# Osmofl2k_adapter_bandpass.net
KiCad netlist of a schematic drawn in EAGLE
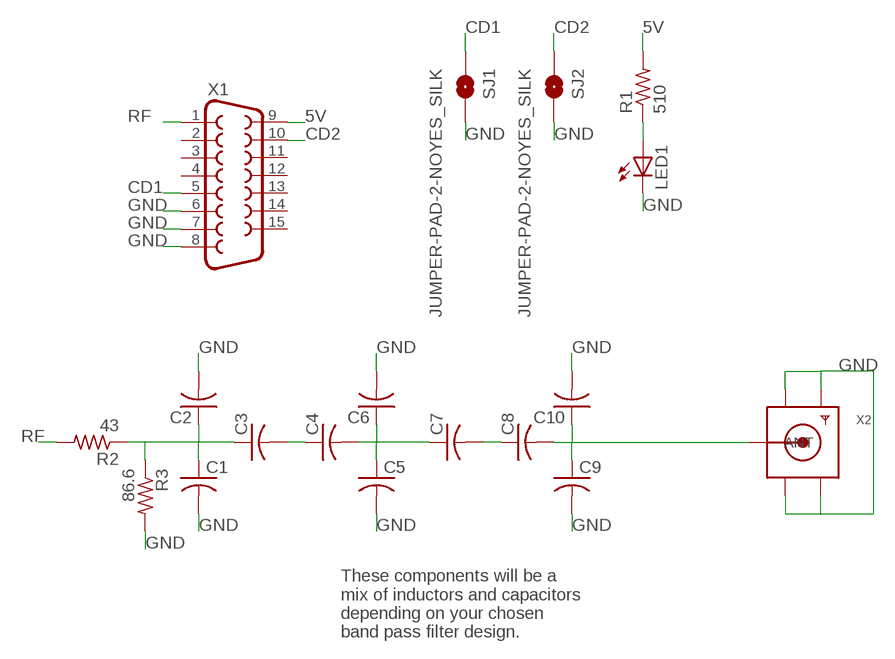
[diagram p0: schematic, sheet 1]

(export (version "E")
  (design (tool "Eeschema 10.0.6"))
  (components
    (comp (ref "C1")
      (value "C-USC0603")
      (footprint "eagle-import:C0603")
      (libsource (lib "eagle-import") (part "C-USC0603"))
    )
    (comp (ref "C2")
      (value "C-USC0402")
      (footprint "eagle-import:C0402")
      (libsource (lib "eagle-import") (part "C-USC0402"))
    )
    (comp (ref "C3")
      (value "C-USC0805")
      (footprint "eagle-import:C0805")
      (libsource (lib "eagle-import") (part "C-USC0805"))
    )
    (comp (ref "C4")
      (value "C-USC0603")
      (footprint "eagle-import:C0603")
      (libsource (lib "eagle-import") (part "C-USC0603"))
    )
    (comp (ref "C5")
      (value "C-USC0603")
      (footprint "eagle-import:C0603")
      (libsource (lib "eagle-import") (part "C-USC0603"))
    )
    (comp (ref "C6")
      (value "C-USC0402")
      (footprint "eagle-import:C0402")
      (libsource (lib "eagle-import") (part "C-USC0402"))
    )
    (comp (ref "C7")
      (value "C-USC0805")
      (footprint "eagle-import:C0805")
      (libsource (lib "eagle-import") (part "C-USC0805"))
    )
    (comp (ref "C8")
      (value "C-USC0603")
      (footprint "eagle-import:C0603")
      (libsource (lib "eagle-import") (part "C-USC0603"))
    )
    (comp (ref "C9")
      (value "C-USC0603")
      (footprint "eagle-import:C0603")
      (libsource (lib "eagle-import") (part "C-USC0603"))
    )
    (comp (ref "C10")
      (value "C-USC0402")
      (footprint "eagle-import:C0402")
      (libsource (lib "eagle-import") (part "C-USC0402"))
    )
    (comp (ref "LED1")
      (value "LEDCHIPLED_0805")
      (footprint "eagle-import:CHIPLED_0805")
      (libsource (lib "eagle-import") (part "LEDCHIPLED_0805"))
    )
    (comp (ref "R1")
      (value "510")
      (footprint "eagle-import:R0805")
      (libsource (lib "eagle-import") (part "R-US_R0805"))
    )
    (comp (ref "R2")
      (value "43")
      (footprint "eagle-import:R0805")
      (libsource (lib "eagle-import") (part "R-US_R0805"))
    )
    (comp (ref "R3")
      (value "86.6")
      (footprint "eagle-import:R0805")
      (libsource (lib "eagle-import") (part "R-US_R0805"))
    )
    (comp (ref "SJ1")
      (value "JUMPER-PAD-2-NOYES_SILK")
      (footprint "eagle-import:PAD-JUMPER-2-NO_YES_SILK")
      (libsource (lib "eagle-import") (part "JUMPER-PAD-2-NOYES_SILK"))
    )
    (comp (ref "SJ2")
      (value "JUMPER-PAD-2-NOYES_SILK")
      (footprint "eagle-import:PAD-JUMPER-2-NO_YES_SILK")
      (libsource (lib "eagle-import") (part "JUMPER-PAD-2-NOYES_SILK"))
    )
    (comp (ref "X1")
      (value "F15HDH")
      (footprint "eagle-import:HDF15H")
      (libsource (lib "eagle-import") (part "F15HDH"))
    )
    (comp (ref "X2")
      (value "SMACONNECTOR_EDGE")
      (footprint "eagle-import:SMA_EDGELAUNCH")
      (libsource (lib "eagle-import") (part "SMACONNECTOR_EDGE"))
    )
  )
  (nets
    (net (code "1") (name "/5V") (class "Default")
      (node (ref "R1") (pin "2") (pinfunction "2_2") (pintype "passive"))
      (node (ref "X1") (pin "9") (pinfunction "9_9") (pintype "passive"))
    )
    (net (code "2") (name "/CD1") (class "Default")
      (node (ref "SJ1") (pin "1") (pinfunction "1_1") (pintype "passive"))
      (node (ref "X1") (pin "5") (pinfunction "5_5") (pintype "passive"))
    )
    (net (code "3") (name "/CD2") (class "Default")
      (node (ref "SJ2") (pin "1") (pinfunction "1_1") (pintype "passive"))
      (node (ref "X1") (pin "10") (pinfunction "10_10") (pintype "passive"))
    )
    (net (code "4") (name "/GND") (class "Default")
      (node (ref "C1") (pin "2") (pinfunction "2_2") (pintype "passive"))
      (node (ref "C10") (pin "2") (pinfunction "2_2") (pintype "passive"))
      (node (ref "C2") (pin "2") (pinfunction "2_2") (pintype "passive"))
      (node (ref "C5") (pin "2") (pinfunction "2_2") (pintype "passive"))
      (node (ref "C6") (pin "2") (pinfunction "2_2") (pintype "passive"))
      (node (ref "C9") (pin "2") (pinfunction "2_2") (pintype "passive"))
      (node (ref "LED1") (pin "C") (pinfunction "C_C") (pintype "passive"))
      (node (ref "R3") (pin "2") (pinfunction "2_2") (pintype "passive"))
      (node (ref "SJ1") (pin "2") (pinfunction "2_2") (pintype "passive"))
      (node (ref "SJ2") (pin "2") (pinfunction "2_2") (pintype "passive"))
      (node (ref "X1") (pin "6") (pinfunction "6_6") (pintype "passive"))
      (node (ref "X1") (pin "7") (pinfunction "7_7") (pintype "passive"))
      (node (ref "X1") (pin "8") (pinfunction "8_8") (pintype "passive"))
      (node (ref "X2") (pin "GND@1") (pinfunction "GND4_GND@1") (pintype "power_in"))
      (node (ref "X2") (pin "GND@2") (pinfunction "GND3_GND@2") (pintype "power_in"))
      (node (ref "X2") (pin "GND@3") (pinfunction "GND2_GND@3") (pintype "power_in"))
      (node (ref "X2") (pin "GND@4") (pinfunction "GND1_GND@4") (pintype "power_in"))
    )
    (net (code "5") (name "/RF") (class "Default")
      (node (ref "R2") (pin "2") (pinfunction "2_2") (pintype "passive"))
      (node (ref "X1") (pin "1") (pinfunction "1_1") (pintype "passive"))
    )
    (net (code "6") (name "Net-(C1-Pad1)") (class "Default")
      (node (ref "C1") (pin "1") (pinfunction "1_1") (pintype "passive"))
      (node (ref "C2") (pin "1") (pinfunction "1_1") (pintype "passive"))
      (node (ref "C3") (pin "1") (pinfunction "1_1") (pintype "passive"))
      (node (ref "R2") (pin "1") (pinfunction "1_1") (pintype "passive"))
      (node (ref "R3") (pin "1") (pinfunction "1_1") (pintype "passive"))
    )
    (net (code "7") (name "Net-(C3-Pad2)") (class "Default")
      (node (ref "C3") (pin "2") (pinfunction "2_2") (pintype "passive"))
      (node (ref "C4") (pin "1") (pinfunction "1_1") (pintype "passive"))
    )
    (net (code "8") (name "Net-(C4-Pad2)") (class "Default")
      (node (ref "C4") (pin "2") (pinfunction "2_2") (pintype "passive"))
      (node (ref "C5") (pin "1") (pinfunction "1_1") (pintype "passive"))
      (node (ref "C6") (pin "1") (pinfunction "1_1") (pintype "passive"))
      (node (ref "C7") (pin "1") (pinfunction "1_1") (pintype "passive"))
    )
    (net (code "9") (name "Net-(C7-Pad2)") (class "Default")
      (node (ref "C7") (pin "2") (pinfunction "2_2") (pintype "passive"))
      (node (ref "C8") (pin "1") (pinfunction "1_1") (pintype "passive"))
    )
    (net (code "10") (name "Net-(LED1-PadA)") (class "Default")
      (node (ref "LED1") (pin "A") (pinfunction "A_A") (pintype "passive"))
      (node (ref "R1") (pin "1") (pinfunction "1_1") (pintype "passive"))
    )
    (net (code "11") (name "Net-(X2-ANT)") (class "Default")
      (node (ref "C10") (pin "1") (pinfunction "1_1") (pintype "passive"))
      (node (ref "C8") (pin "2") (pinfunction "2_2") (pintype "passive"))
      (node (ref "C9") (pin "1") (pinfunction "1_1") (pintype "passive"))
      (node (ref "X2") (pin "P") (pinfunction "ANT_P") (pintype "bidirectional"))
    )
    (net (code "12") (name "unconnected-(X1-Pad2)") (class "Default")
      (node (ref "X1") (pin "2") (pinfunction "2_2") (pintype "passive"))
    )
    (net (code "13") (name "unconnected-(X1-Pad3)") (class "Default")
      (node (ref "X1") (pin "3") (pinfunction "3_3") (pintype "passive"))
    )
    (net (code "14") (name "unconnected-(X1-Pad4)") (class "Default")
      (node (ref "X1") (pin "4") (pinfunction "4_4") (pintype "passive"))
    )
    (net (code "15") (name "unconnected-(X1-Pad11)") (class "Default")
      (node (ref "X1") (pin "11") (pinfunction "11_11") (pintype "passive"))
    )
    (net (code "16") (name "unconnected-(X1-Pad12)") (class "Default")
      (node (ref "X1") (pin "12") (pinfunction "12_12") (pintype "passive"))
    )
    (net (code "17") (name "unconnected-(X1-Pad13)") (class "Default")
      (node (ref "X1") (pin "13") (pinfunction "13_13") (pintype "passive"))
    )
    (net (code "18") (name "unconnected-(X1-Pad14)") (class "Default")
      (node (ref "X1") (pin "14") (pinfunction "14_14") (pintype "passive"))
    )
    (net (code "19") (name "unconnected-(X1-Pad15)") (class "Default")
      (node (ref "X1") (pin "15") (pinfunction "15_15") (pintype "passive"))
    )
  )
)
